# CAN.net
KiCad netlist of a schematic drawn in Altium Designer
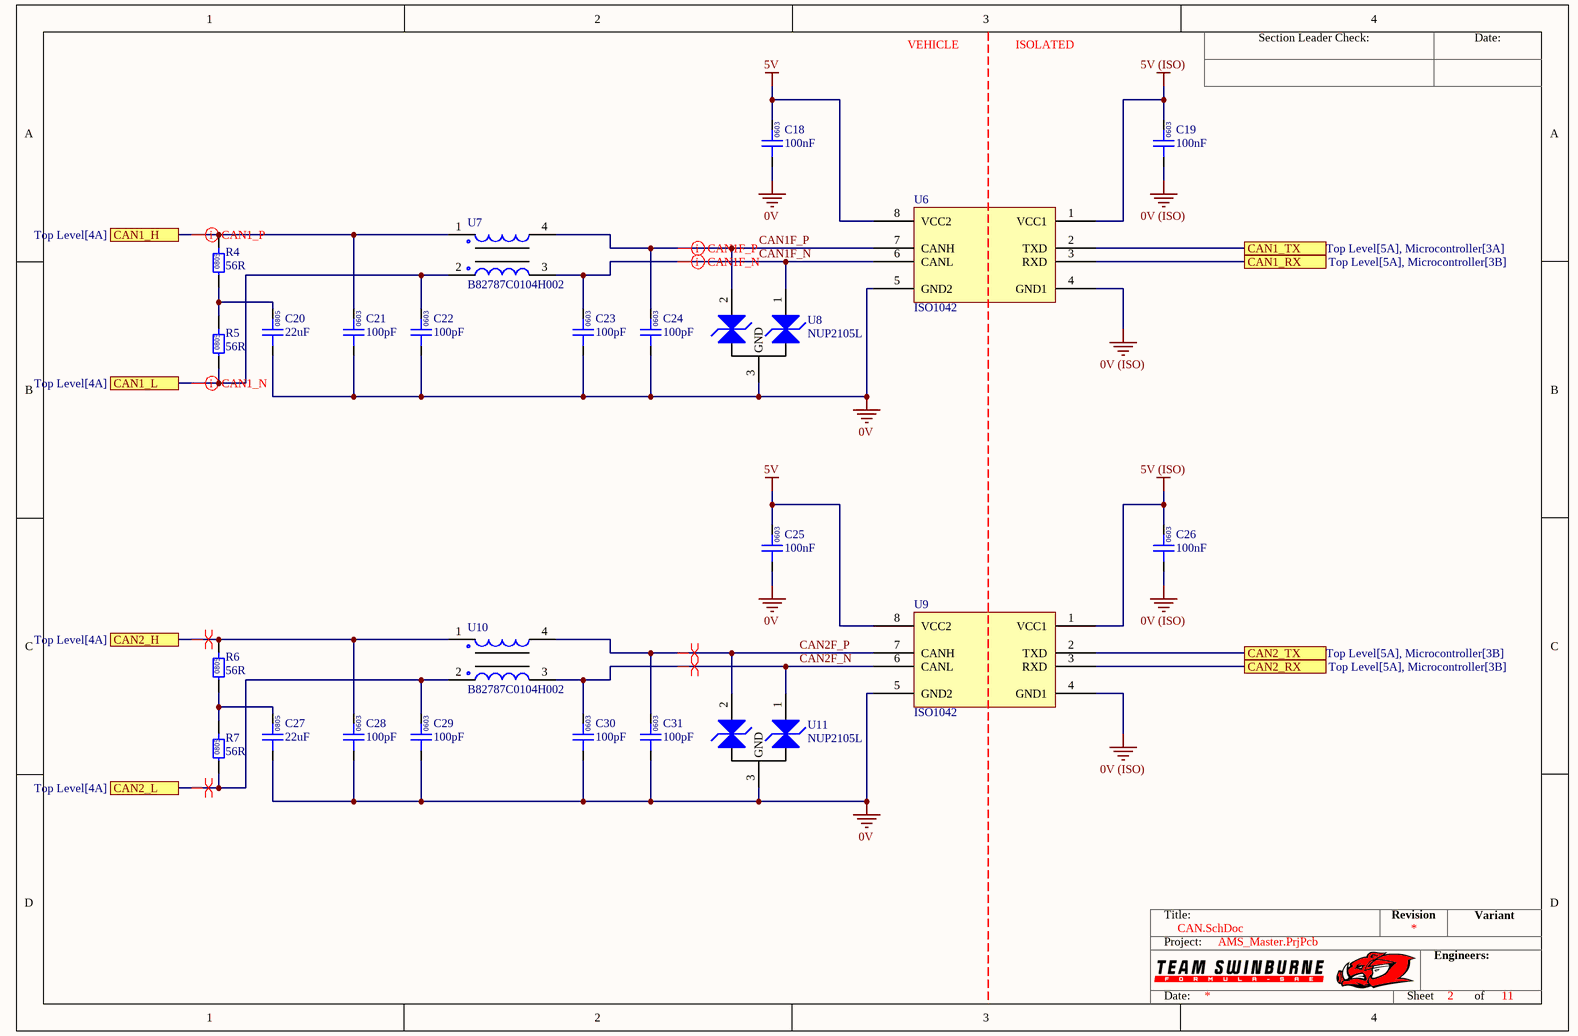
[diagram p0: CAN.SchDoc]

(export (version "E")
  (design (tool "Eeschema 10.0.6"))
  (components
    (comp (ref "C18")
      (value "100nF")
      (footprint "0603")
      (fields
        (field (name "PART NUMBER") "GCM188L81H104KA57D")
        (field (name "MANUFACTURER") "muRata")
        (field (name "TOLERANCE") "±10%")
      )
      (libsource (lib "ts_standard_library") (part "Capacitor 0603"))
    )
    (comp (ref "C19")
      (value "100nF")
      (footprint "0603")
      (fields
        (field (name "PART NUMBER") "GCM188L81H104KA57D")
        (field (name "MANUFACTURER") "muRata")
        (field (name "TOLERANCE") "±10%")
      )
      (libsource (lib "ts_standard_library") (part "Capacitor 0603"))
    )
    (comp (ref "C20")
      (value "22uF")
      (footprint "0805")
      (fields
        (field (name "PART NUMBER") "GRM21BR61A226ME51L")
        (field (name "MANUFACTURER") "muRata")
        (field (name "TOLERANCE") "20%")
      )
      (libsource (lib "ts_standard_library") (part "Capacitor 0805"))
    )
    (comp (ref "C21")
      (value "100pF")
      (footprint "0603")
      (fields
        (field (name "PART NUMBER") "GRM1885C1H101JA01D")
        (field (name "MANUFACTURER") "Murata Electronics")
        (field (name "TOLERANCE") "±5%")
      )
      (libsource (lib "ts_standard_library") (part "Capacitor 0603"))
    )
    (comp (ref "C22")
      (value "100pF")
      (footprint "0603")
      (fields
        (field (name "PART NUMBER") "GRM1885C1H101JA01D")
        (field (name "MANUFACTURER") "Murata Electronics")
        (field (name "TOLERANCE") "±5%")
      )
      (libsource (lib "ts_standard_library") (part "Capacitor 0603"))
    )
    (comp (ref "C23")
      (value "100pF")
      (footprint "0603")
      (fields
        (field (name "PART NUMBER") "GRM1885C1H101JA01D")
        (field (name "MANUFACTURER") "Murata Electronics")
        (field (name "TOLERANCE") "±5%")
      )
      (libsource (lib "ts_standard_library") (part "Capacitor 0603"))
    )
    (comp (ref "C24")
      (value "100pF")
      (footprint "0603")
      (fields
        (field (name "PART NUMBER") "GRM1885C1H101JA01D")
        (field (name "MANUFACTURER") "Murata Electronics")
        (field (name "TOLERANCE") "±5%")
      )
      (libsource (lib "ts_standard_library") (part "Capacitor 0603"))
    )
    (comp (ref "C25")
      (value "100nF")
      (footprint "0603")
      (fields
        (field (name "PART NUMBER") "GCM188L81H104KA57D")
        (field (name "MANUFACTURER") "muRata")
        (field (name "TOLERANCE") "±10%")
      )
      (libsource (lib "ts_standard_library") (part "Capacitor 0603"))
    )
    (comp (ref "C26")
      (value "100nF")
      (footprint "0603")
      (fields
        (field (name "PART NUMBER") "GCM188L81H104KA57D")
        (field (name "MANUFACTURER") "muRata")
        (field (name "TOLERANCE") "±10%")
      )
      (libsource (lib "ts_standard_library") (part "Capacitor 0603"))
    )
    (comp (ref "C27")
      (value "22uF")
      (footprint "0805")
      (fields
        (field (name "PART NUMBER") "GRM21BR61A226ME51L")
        (field (name "MANUFACTURER") "muRata")
        (field (name "TOLERANCE") "20%")
      )
      (libsource (lib "ts_standard_library") (part "Capacitor 0805"))
    )
    (comp (ref "C28")
      (value "100pF")
      (footprint "0603")
      (fields
        (field (name "PART NUMBER") "GRM1885C1H101JA01D")
        (field (name "MANUFACTURER") "Murata Electronics")
        (field (name "TOLERANCE") "±5%")
      )
      (libsource (lib "ts_standard_library") (part "Capacitor 0603"))
    )
    (comp (ref "C29")
      (value "100pF")
      (footprint "0603")
      (fields
        (field (name "PART NUMBER") "GRM1885C1H101JA01D")
        (field (name "MANUFACTURER") "Murata Electronics")
        (field (name "TOLERANCE") "±5%")
      )
      (libsource (lib "ts_standard_library") (part "Capacitor 0603"))
    )
    (comp (ref "C30")
      (value "100pF")
      (footprint "0603")
      (fields
        (field (name "PART NUMBER") "GRM1885C1H101JA01D")
        (field (name "MANUFACTURER") "Murata Electronics")
        (field (name "TOLERANCE") "±5%")
      )
      (libsource (lib "ts_standard_library") (part "Capacitor 0603"))
    )
    (comp (ref "C31")
      (value "100pF")
      (footprint "0603")
      (fields
        (field (name "PART NUMBER") "GRM1885C1H101JA01D")
        (field (name "MANUFACTURER") "Murata Electronics")
        (field (name "TOLERANCE") "±5%")
      )
      (libsource (lib "ts_standard_library") (part "Capacitor 0603"))
    )
    (comp (ref "R4")
      (value "56R")
      (footprint "0805")
      (fields
        (field (name "PART NUMBER") "RC0805FR0756RL")
        (field (name "MANUFACTURER") "YAGEO")
        (field (name "TOLERANCE") "0.01")
      )
      (libsource (lib "ts_standard_library") (part "Resistor 0805"))
    )
    (comp (ref "R5")
      (value "56R")
      (footprint "0805")
      (fields
        (field (name "PART NUMBER") "RC0805FR0756RL")
        (field (name "MANUFACTURER") "YAGEO")
        (field (name "TOLERANCE") "0.01")
      )
      (libsource (lib "ts_standard_library") (part "Resistor 0805"))
    )
    (comp (ref "R6")
      (value "56R")
      (footprint "0805")
      (fields
        (field (name "PART NUMBER") "RC0805FR0756RL")
        (field (name "MANUFACTURER") "YAGEO")
        (field (name "TOLERANCE") "0.01")
      )
      (libsource (lib "ts_standard_library") (part "Resistor 0805"))
    )
    (comp (ref "R7")
      (value "56R")
      (footprint "0805")
      (fields
        (field (name "PART NUMBER") "RC0805FR0756RL")
        (field (name "MANUFACTURER") "YAGEO")
        (field (name "TOLERANCE") "0.01")
      )
      (libsource (lib "ts_standard_library") (part "Resistor 0805"))
    )
    (comp (ref "U6")
      (value "ISO1042")
      (footprint "TI-SOIC-8")
      (description "IC CAN TRANSCEIVER 1/1 8SOIC")
      (fields
        (field (name "MANUFACTURER") "Texas Instruments")
        (field (name "DIGIKEY PART NUMBER") "296-ISO1042BQDWVQ1-ND")
      )
      (libsource (lib "ts_standard_library") (part "ISO1042"))
    )
    (comp (ref "U7")
      (value "B82787C0104H002")
      (footprint "TDK 4-PC Pad")
      (fields
        (field (name "MANUFACTURER") "EPCOS (TDK)")
        (field (name "DIGIKEY PART NUMBER") "495-4598-1-ND")
      )
      (libsource (lib "ts_standard_library") (part "B82787C0104H002"))
    )
    (comp (ref "U8")
      (value "NUP2105L")
      (footprint "ON SOT-23")
      (description "Dual Line CAN Bus Protector")
      (fields
        (field (name "MANUFACTURER") "ON Semiconductor")
        (field (name "DIGIKEY PART NUMBER") "NUP2105LT1GOSCT-ND")
      )
      (libsource (lib "ts_standard_library") (part "NUP2105L"))
    )
    (comp (ref "U9")
      (value "ISO1042")
      (footprint "TI-SOIC-8")
      (description "IC CAN TRANSCEIVER 1/1 8SOIC")
      (fields
        (field (name "MANUFACTURER") "Texas Instruments")
        (field (name "DIGIKEY PART NUMBER") "296-ISO1042BQDWVQ1-ND")
      )
      (libsource (lib "ts_standard_library") (part "ISO1042"))
    )
    (comp (ref "U10")
      (value "B82787C0104H002")
      (footprint "TDK 4-PC Pad")
      (fields
        (field (name "MANUFACTURER") "EPCOS (TDK)")
        (field (name "DIGIKEY PART NUMBER") "495-4598-1-ND")
      )
      (libsource (lib "ts_standard_library") (part "B82787C0104H002"))
    )
    (comp (ref "U11")
      (value "NUP2105L")
      (footprint "ON SOT-23")
      (description "Dual Line CAN Bus Protector")
      (fields
        (field (name "MANUFACTURER") "ON Semiconductor")
        (field (name "DIGIKEY PART NUMBER") "NUP2105LT1GOSCT-ND")
      )
      (libsource (lib "ts_standard_library") (part "NUP2105L"))
    )
  )
  (nets
    (net (code "1") (name "/CAN1F_N") (class "Default")
      (node (ref "C23") (pin "2") (pinfunction "2_2") (pintype "passive"))
      (node (ref "U6") (pin "6") (pinfunction "CANL_6") (pintype "passive"))
      (node (ref "U7") (pin "3") (pinfunction "3_3") (pintype "passive"))
      (node (ref "U8") (pin "1") (pinfunction "CAN_H_1") (pintype "passive"))
    )
    (net (code "2") (name "/CAN1F_P") (class "Default")
      (node (ref "C24") (pin "2") (pinfunction "2_2") (pintype "passive"))
      (node (ref "U6") (pin "7") (pinfunction "CANH_7") (pintype "passive"))
      (node (ref "U7") (pin "4") (pinfunction "4_4") (pintype "passive"))
      (node (ref "U8") (pin "2") (pinfunction "CAN_L_2") (pintype "passive"))
    )
    (net (code "3") (name "/CAN1_H") (class "Default")
      (node (ref "C21") (pin "2") (pinfunction "2_2") (pintype "passive"))
      (node (ref "R4") (pin "2") (pinfunction "2_2") (pintype "passive"))
      (node (ref "U7") (pin "1") (pinfunction "1_1") (pintype "passive"))
    )
    (net (code "4") (name "/CAN1_L") (class "Default")
      (node (ref "C22") (pin "2") (pinfunction "2_2") (pintype "passive"))
      (node (ref "R5") (pin "1") (pinfunction "1_1") (pintype "passive"))
      (node (ref "U7") (pin "2") (pinfunction "2_2") (pintype "passive"))
    )
    (net (code "5") (name "/CAN1_RX") (class "Default")
      (node (ref "U6") (pin "3") (pinfunction "RXD_3") (pintype "passive"))
    )
    (net (code "6") (name "/CAN1_TX") (class "Default")
      (node (ref "U6") (pin "2") (pinfunction "TXD_2") (pintype "passive"))
    )
    (net (code "7") (name "/CAN2F_N") (class "Default")
      (node (ref "C30") (pin "2") (pinfunction "2_2") (pintype "passive"))
      (node (ref "U10") (pin "3") (pinfunction "3_3") (pintype "passive"))
      (node (ref "U11") (pin "1") (pinfunction "CAN_H_1") (pintype "passive"))
      (node (ref "U9") (pin "6") (pinfunction "CANL_6") (pintype "passive"))
    )
    (net (code "8") (name "/CAN2F_P") (class "Default")
      (node (ref "C31") (pin "2") (pinfunction "2_2") (pintype "passive"))
      (node (ref "U10") (pin "4") (pinfunction "4_4") (pintype "passive"))
      (node (ref "U11") (pin "2") (pinfunction "CAN_L_2") (pintype "passive"))
      (node (ref "U9") (pin "7") (pinfunction "CANH_7") (pintype "passive"))
    )
    (net (code "9") (name "/CAN2_H") (class "Default")
      (node (ref "C28") (pin "2") (pinfunction "2_2") (pintype "passive"))
      (node (ref "R6") (pin "2") (pinfunction "2_2") (pintype "passive"))
      (node (ref "U10") (pin "1") (pinfunction "1_1") (pintype "passive"))
    )
    (net (code "10") (name "/CAN2_L") (class "Default")
      (node (ref "C29") (pin "2") (pinfunction "2_2") (pintype "passive"))
      (node (ref "R7") (pin "1") (pinfunction "1_1") (pintype "passive"))
      (node (ref "U10") (pin "2") (pinfunction "2_2") (pintype "passive"))
    )
    (net (code "11") (name "/CAN2_RX") (class "Default")
      (node (ref "U9") (pin "3") (pinfunction "RXD_3") (pintype "passive"))
    )
    (net (code "12") (name "/CAN2_TX") (class "Default")
      (node (ref "U9") (pin "2") (pinfunction "TXD_2") (pintype "passive"))
    )
    (net (code "13") (name "0V") (class "Default")
      (node (ref "C18") (pin "1") (pinfunction "1_1") (pintype "passive"))
      (node (ref "C20") (pin "1") (pinfunction "1_1") (pintype "passive"))
      (node (ref "C21") (pin "1") (pinfunction "1_1") (pintype "passive"))
      (node (ref "C22") (pin "1") (pinfunction "1_1") (pintype "passive"))
      (node (ref "C23") (pin "1") (pinfunction "1_1") (pintype "passive"))
      (node (ref "C24") (pin "1") (pinfunction "1_1") (pintype "passive"))
      (node (ref "C25") (pin "1") (pinfunction "1_1") (pintype "passive"))
      (node (ref "C27") (pin "1") (pinfunction "1_1") (pintype "passive"))
      (node (ref "C28") (pin "1") (pinfunction "1_1") (pintype "passive"))
      (node (ref "C29") (pin "1") (pinfunction "1_1") (pintype "passive"))
      (node (ref "C30") (pin "1") (pinfunction "1_1") (pintype "passive"))
      (node (ref "C31") (pin "1") (pinfunction "1_1") (pintype "passive"))
      (node (ref "U11") (pin "3") (pinfunction "GND_3") (pintype "passive"))
      (node (ref "U6") (pin "5") (pinfunction "GND2_5") (pintype "passive"))
      (node (ref "U8") (pin "3") (pinfunction "GND_3") (pintype "passive"))
      (node (ref "U9") (pin "5") (pinfunction "GND2_5") (pintype "passive"))
    )
    (net (code "14") (name "0V (ISO)") (class "Default")
      (node (ref "C19") (pin "1") (pinfunction "1_1") (pintype "passive"))
      (node (ref "C26") (pin "1") (pinfunction "1_1") (pintype "passive"))
      (node (ref "U6") (pin "4") (pinfunction "GND1_4") (pintype "passive"))
      (node (ref "U9") (pin "4") (pinfunction "GND1_4") (pintype "passive"))
    )
    (net (code "15") (name "5V") (class "Default")
      (node (ref "C18") (pin "2") (pinfunction "2_2") (pintype "passive"))
      (node (ref "C25") (pin "2") (pinfunction "2_2") (pintype "passive"))
      (node (ref "U6") (pin "8") (pinfunction "VCC2_8") (pintype "passive"))
      (node (ref "U9") (pin "8") (pinfunction "VCC2_8") (pintype "passive"))
    )
    (net (code "16") (name "5V (ISO)") (class "Default")
      (node (ref "C19") (pin "2") (pinfunction "2_2") (pintype "passive"))
      (node (ref "C26") (pin "2") (pinfunction "2_2") (pintype "passive"))
      (node (ref "U6") (pin "1") (pinfunction "VCC1_1") (pintype "passive"))
      (node (ref "U9") (pin "1") (pinfunction "VCC1_1") (pintype "passive"))
    )
    (net (code "17") (name "Net-(C20-Pad2)") (class "Default")
      (node (ref "C20") (pin "2") (pinfunction "2_2") (pintype "passive"))
      (node (ref "R4") (pin "1") (pinfunction "1_1") (pintype "passive"))
      (node (ref "R5") (pin "2") (pinfunction "2_2") (pintype "passive"))
    )
    (net (code "18") (name "Net-(C27-Pad2)") (class "Default")
      (node (ref "C27") (pin "2") (pinfunction "2_2") (pintype "passive"))
      (node (ref "R6") (pin "1") (pinfunction "1_1") (pintype "passive"))
      (node (ref "R7") (pin "2") (pinfunction "2_2") (pintype "passive"))
    )
  )
)
